# CAN1.net
KiCad netlist of a schematic drawn in Altium Designer
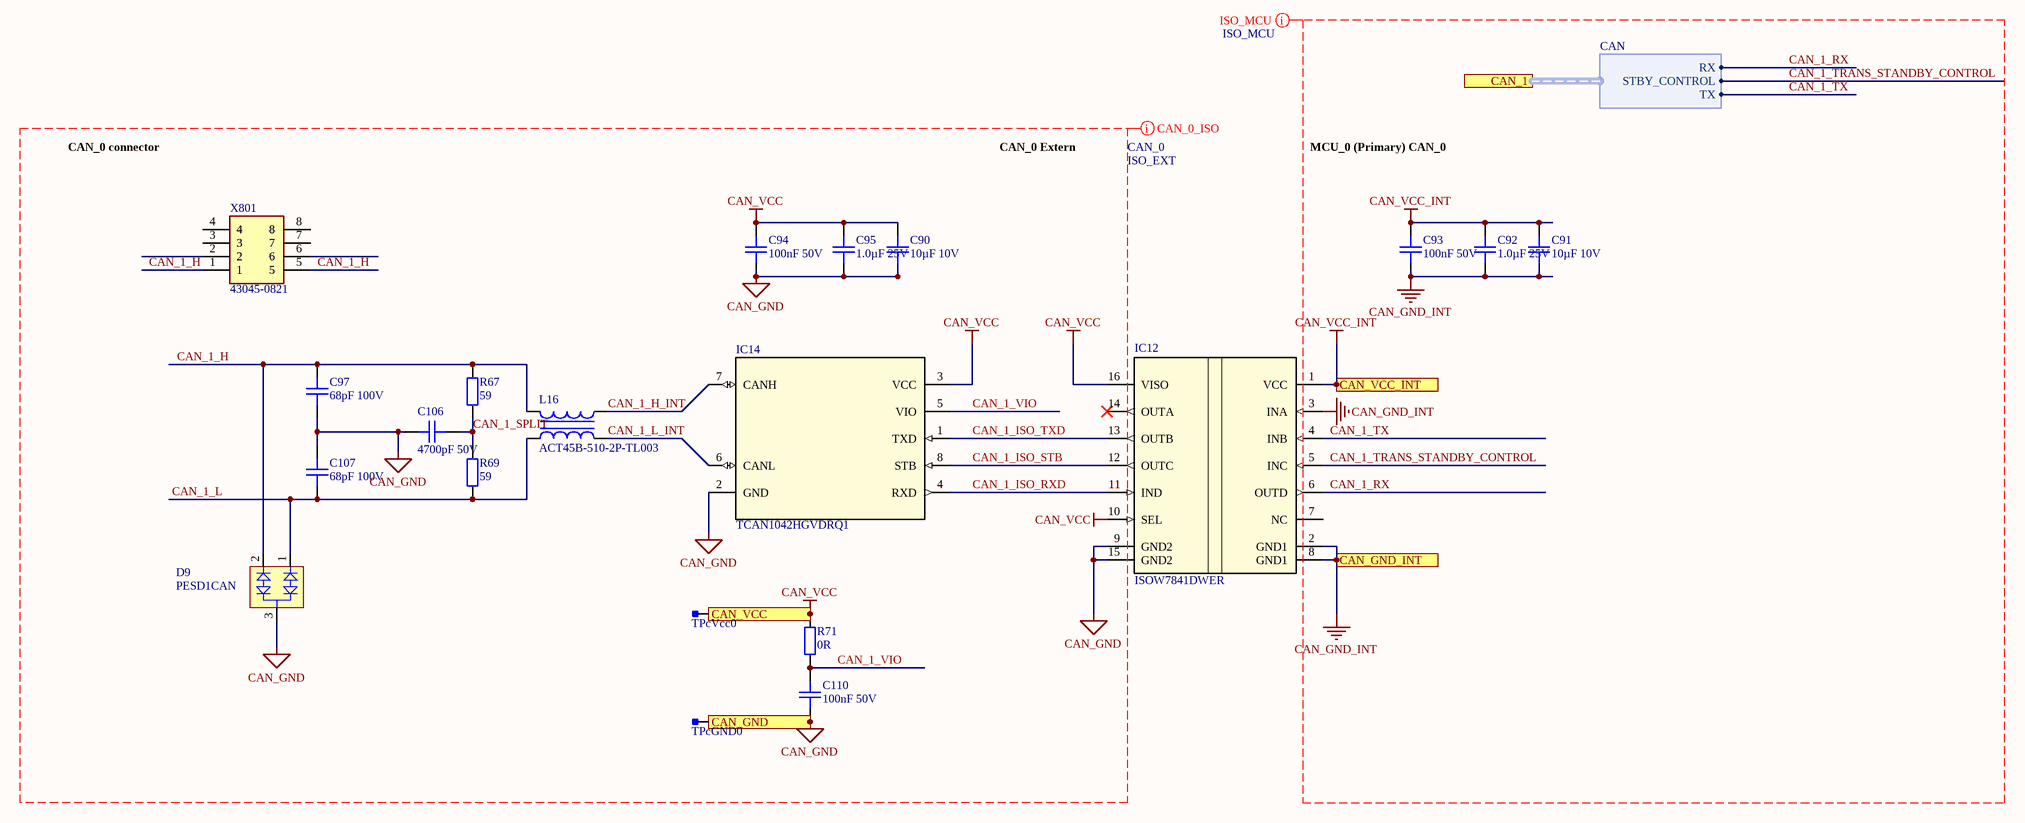
[diagram p0: CAN1.SchDoc]

(export (version "E")
  (design (tool "Eeschema 10.0.6"))
  (components
    (comp (ref "C90")
      (value "10µF 10V")
      (footprint "0805C")
      (description "Ceramic, 10µF, ±10%, 10V, X7R, –55 to 125°C, 0805 (2012),RoHS, Automotive")
      (fields (field (name "PART NUMBER") "GCJ21BR71A106KE01") (field (name "TOLERANCE") "±10%"))
      (libsource (lib "master-010106") (part "gen_C_ceramic_10u_10V_X7R_0805"))
    )
    (comp (ref "C91")
      (value "10µF 10V")
      (footprint "0805C")
      (description "Ceramic, 10µF, ±10%, 10V, X7R, –55 to 125°C, 0805 (2012),RoHS, Automotive")
      (fields (field (name "PART NUMBER") "GCJ21BR71A106KE01") (field (name "TOLERANCE") "±10%"))
      (libsource (lib "master-010106") (part "gen_C_ceramic_10u_10V_X7R_0805"))
    )
    (comp (ref "C92")
      (value "1.0µF 25V")
      (footprint "0603C")
      (description "Ceramic, 1.0µF, ±10%, 25V, X7R, –55 to 125°C, 0603 (1608),RoHS, Automotive")
      (fields (field (name "PART NUMBER") "GCJ188R71E105KA01") (field (name "TOLERANCE") "±10%"))
      (libsource (lib "master-010106") (part "gen_C_ceramic_1u_25V_X7R_0603"))
    )
    (comp (ref "C93")
      (value "100nF 50V")
      (footprint "0603C")
      (description "Ceramic, 100nF, ±10%, 50V, X7R, –55 to 125°C, 0603 (1608),RoHS, Automotive")
      (fields (field (name "PART NUMBER") "GCJ188R71H104KA12") (field (name "TOLERANCE") "±10%"))
      (libsource (lib "master-010106") (part "C"))
    )
    (comp (ref "C94")
      (value "100nF 50V")
      (footprint "0603C")
      (description "Ceramic, 100nF, ±10%, 50V, X7R, –55 to 125°C, 0603 (1608),RoHS, Automotive")
      (fields (field (name "PART NUMBER") "GCJ188R71H104KA12") (field (name "TOLERANCE") "±10%"))
      (libsource (lib "master-010106") (part "C"))
    )
    (comp (ref "C95")
      (value "1.0µF 25V")
      (footprint "0603C")
      (description "Ceramic, 1.0µF, ±10%, 25V, X7R, –55 to 125°C, 0603 (1608),RoHS, Automotive")
      (fields (field (name "PART NUMBER") "GCJ188R71E105KA01") (field (name "TOLERANCE") "±10%"))
      (libsource (lib "master-010106") (part "gen_C_ceramic_1u_25V_X7R_0603"))
    )
    (comp (ref "C97")
      (value "68pF 100V")
      (footprint "0603C")
      (description "Ceramic, 68pF, ±5%, 100V, X7R, 25 to 125°C, 0603 (1608),RoHS, Automotive")
      (fields (field (name "PART NUMBER") "GCM1885C2A680JA16") (field (name "TOLERANCE") "±5%"))
      (libsource (lib "master-010106") (part "gen_C_ceramic_68p_100V_X7R_0603"))
    )
    (comp (ref "C106")
      (value "4700pF 50V")
      (footprint "0603C")
      (description "Ceramic, 4700pF, 0603, ±5%, 50V, C0G")
      (fields (field (name "PART NUMBER") "GRT1885C1H472JA02"))
      (libsource (lib "master-010106") (part "C"))
    )
    (comp (ref "C107")
      (value "68pF 100V")
      (footprint "0603C")
      (description "Ceramic, 68pF, ±5%, 100V, X7R, 25 to 125°C, 0603 (1608),RoHS, Automotive")
      (fields (field (name "PART NUMBER") "GCM1885C2A680JA16") (field (name "TOLERANCE") "±5%"))
      (libsource (lib "master-010106") (part "gen_C_ceramic_68p_100V_X7R_0603"))
    )
    (comp (ref "C110")
      (value "100nF 50V")
      (footprint "0603C")
      (description "Ceramic, 100nF, ±10%, 50V, X7R, –55 to 125°C, 0603 (1608),RoHS, Automotive")
      (fields (field (name "PART NUMBER") "GCJ188R71H104KA12") (field (name "TOLERANCE") "±10%"))
      (libsource (lib "master-010106") (part "C"))
    )
    (comp (ref "D9")
      (value "PESD1CAN")
      (footprint "NXP-SOT23-3_V")
      (description "CAN Bus ESD Protection Diode, 200 W, 24 V, -65 to 150 degC, 3-Pin SOT23, RoHS, Tape and Reel")
      (fields (field (name "MANUFACTURER") "NXP Semiconductors"))
      (libsource (lib "Altium Content Vault") (part "NXP-PESD1CAN-SOT23-3"))
    )
    (comp (ref "IC12")
      (value "ISOW7841DWER")
      (footprint "DWE0016A")
      (description "Imported")
      (fields (field (name "MANUFACTURER") "Texas Instruments"))
      (libsource (lib "ti-import") (part "ISOW7841DWER"))
    )
    (comp (ref "IC14")
      (value "TCAN1042HGVDRQ1")
      (footprint "D0008A_N")
      (description "Imported")
      (fields (field (name "PARTNUMBER") "TCAN1042HGVDQ1") (field (name "MANUFACTURER") "Texas Instruments"))
      (libsource (lib "ti-import") (part "TCAN1042HGVDRQ1"))
    )
    (comp (ref "L16")
      (value "ACT45B-510-2P-TL003")
      (footprint "TDK-ACT45B-510-2P-TL003-4_V")
      (fields (field (name "MANUFACTURER") "TDK"))
      (libsource (lib "Altium Content Vault") (part "TDK-ACXXXXX-XXX-2P-T000-4"))
    )
    (comp (ref "R67")
      (value "59")
      (footprint "0805R")
      (description "SMD Resistor 59R 0805")
      (fields (field (name "PART NUMBER") "gen_R_62R_0603") (field (name "TOLERANCE") "1%"))
      (libsource (lib "master-010106") (part "gen_R_59R_0805"))
    )
    (comp (ref "R69")
      (value "59")
      (footprint "0805R")
      (description "SMD Resistor 59R 0805")
      (fields (field (name "PART NUMBER") "gen_R_62R_0603") (field (name "TOLERANCE") "1%"))
      (libsource (lib "master-010106") (part "gen_R_59R_0805"))
    )
    (comp (ref "R71")
      (value "0R")
      (footprint "0603R")
      (description "SMD Resistor 0R 0603")
      (fields (field (name "PART NUMBER") "gen_R_0R_0603") (field (name "POWER") "0.1W"))
      (libsource (lib "master-010106") (part "gen_R_0R_0603"))
    )
    (comp (ref "TPcGND0")
      (value "Testpoint_Square")
      (footprint "Testpoint_S1")
      (description "Testpoint, square")
      (libsource (lib "OE750") (part "Testpoint_Square"))
    )
    (comp (ref "TPcVcc0")
      (value "Testpoint_Square")
      (footprint "Testpoint_S1")
      (description "Testpoint, square")
      (libsource (lib "OE750") (part "Testpoint_Square"))
    )
    (comp (ref "X801")
      (value "43045-0821")
      (footprint "43045-0821")
      (fields (field (name "MOUSER PART NUMBER") "538-43045-0821"))
      (libsource (lib "SamacSys") (part "43045-0821"))
    )
  )
  (nets
    (net (code "2") (name "/CAN_1_H") (class "Default")
      (node (ref "C97") (pin "2") (pinfunction "2_2") (pintype "passive"))
      (node (ref "D9") (pin "2") (pinfunction "K2_2") (pintype "passive"))
      (node (ref "L16") (pin "2") (pinfunction "2_2") (pintype "passive"))
      (node (ref "R67") (pin "2") (pinfunction "2_2") (pintype "passive"))
      (node (ref "X801") (pin "1") (pinfunction "1_1") (pintype "passive"))
      (node (ref "X801") (pin "5") (pinfunction "5_5") (pintype "passive"))
    )
    (net (code "3") (name "/CAN_1_H_INT") (class "Default")
      (node (ref "IC14") (pin "7") (pinfunction "CANH_7") (pintype "bidirectional"))
      (node (ref "L16") (pin "3") (pinfunction "3_3") (pintype "passive"))
    )
    (net (code "4") (name "/CAN_1_ISO_RXD") (class "Default")
      (node (ref "IC12") (pin "11") (pinfunction "IND_11") (pintype "input"))
      (node (ref "IC14") (pin "4") (pinfunction "RXD_4") (pintype "output"))
    )
    (net (code "5") (name "/CAN_1_ISO_STB") (class "Default")
      (node (ref "IC12") (pin "12") (pinfunction "OUTC_12") (pintype "output"))
      (node (ref "IC14") (pin "8") (pinfunction "STB_8") (pintype "input"))
    )
    (net (code "6") (name "/CAN_1_ISO_TXD") (class "Default")
      (node (ref "IC12") (pin "13") (pinfunction "OUTB_13") (pintype "output"))
      (node (ref "IC14") (pin "1") (pinfunction "TXD_1") (pintype "input"))
    )
    (net (code "7") (name "/CAN_1_L") (class "Default")
      (node (ref "C107") (pin "1") (pinfunction "1_1") (pintype "passive"))
      (node (ref "D9") (pin "1") (pinfunction "K1_1") (pintype "passive"))
      (node (ref "L16") (pin "1") (pinfunction "1_1") (pintype "passive"))
      (node (ref "R69") (pin "1") (pinfunction "1_1") (pintype "passive"))
    )
    (net (code "8") (name "/CAN_1_L_INT") (class "Default")
      (node (ref "IC14") (pin "6") (pinfunction "CANL_6") (pintype "bidirectional"))
      (node (ref "L16") (pin "4") (pinfunction "4_4") (pintype "passive"))
    )
    (net (code "9") (name "/CAN_1_RX") (class "Default")
      (node (ref "IC12") (pin "6") (pinfunction "OUTD_6") (pintype "output"))
    )
    (net (code "10") (name "/CAN_1_SPLIT") (class "Default")
      (node (ref "C106") (pin "2") (pinfunction "2_2") (pintype "passive"))
      (node (ref "R67") (pin "1") (pinfunction "1_1") (pintype "passive"))
      (node (ref "R69") (pin "2") (pinfunction "2_2") (pintype "passive"))
    )
    (net (code "11") (name "/CAN_1_TRANS_STANDBY_CONTROL") (class "Default")
      (node (ref "IC12") (pin "5") (pinfunction "INC_5") (pintype "input"))
    )
    (net (code "12") (name "/CAN_1_TX") (class "Default")
      (node (ref "IC12") (pin "4") (pinfunction "INB_4") (pintype "input"))
    )
    (net (code "13") (name "/CAN_1_VIO") (class "Default")
      (node (ref "C110") (pin "2") (pinfunction "2_2") (pintype "passive"))
      (node (ref "IC14") (pin "5") (pinfunction "VIO_5") (pintype "power_in"))
      (node (ref "R71") (pin "2") (pinfunction "2_2") (pintype "passive"))
    )
    (net (code "15") (name "CAN_GND") (class "Default")
      (node (ref "C106") (pin "1") (pinfunction "1_1") (pintype "passive"))
      (node (ref "C107") (pin "2") (pinfunction "2_2") (pintype "passive"))
      (node (ref "C110") (pin "1") (pinfunction "1_1") (pintype "passive"))
      (node (ref "C90") (pin "2") (pinfunction "2_2") (pintype "passive"))
      (node (ref "C94") (pin "1") (pinfunction "1_1") (pintype "passive"))
      (node (ref "C95") (pin "1") (pinfunction "1_1") (pintype "passive"))
      (node (ref "C97") (pin "1") (pinfunction "1_1") (pintype "passive"))
      (node (ref "D9") (pin "3") (pinfunction "C_3") (pintype "passive"))
      (node (ref "IC12") (pin "15") (pinfunction "GND2_15") (pintype "power_in"))
      (node (ref "IC12") (pin "9") (pinfunction "GND2_9") (pintype "power_in"))
      (node (ref "IC14") (pin "2") (pinfunction "GND_2") (pintype "power_in"))
      (node (ref "TPcGND0") (pin "1") (pinfunction "1_1") (pintype "passive"))
    )
    (net (code "16") (name "CAN_GND_INT") (class "Default")
      (node (ref "C91") (pin "2") (pinfunction "2_2") (pintype "passive"))
      (node (ref "C92") (pin "1") (pinfunction "1_1") (pintype "passive"))
      (node (ref "C93") (pin "1") (pinfunction "1_1") (pintype "passive"))
      (node (ref "IC12") (pin "2") (pinfunction "GND1_2") (pintype "power_in"))
      (node (ref "IC12") (pin "3") (pinfunction "INA_3") (pintype "input"))
      (node (ref "IC12") (pin "8") (pinfunction "GND1_8") (pintype "power_in"))
    )
    (net (code "17") (name "CAN_VCC") (class "Default")
      (node (ref "C90") (pin "1") (pinfunction "1_1") (pintype "passive"))
      (node (ref "C94") (pin "2") (pinfunction "2_2") (pintype "passive"))
      (node (ref "C95") (pin "2") (pinfunction "2_2") (pintype "passive"))
      (node (ref "IC12") (pin "10") (pinfunction "SEL_10") (pintype "input"))
      (node (ref "IC12") (pin "16") (pinfunction "VISO_16") (pintype "power_in"))
      (node (ref "IC14") (pin "3") (pinfunction "VCC_3") (pintype "power_in"))
      (node (ref "R71") (pin "1") (pinfunction "1_1") (pintype "passive"))
      (node (ref "TPcVcc0") (pin "1") (pinfunction "1_1") (pintype "passive"))
    )
    (net (code "18") (name "CAN_VCC_INT") (class "Default")
      (node (ref "C91") (pin "1") (pinfunction "1_1") (pintype "passive"))
      (node (ref "C92") (pin "2") (pinfunction "2_2") (pintype "passive"))
      (node (ref "C93") (pin "2") (pinfunction "2_2") (pintype "passive"))
      (node (ref "IC12") (pin "1") (pinfunction "VCC_1") (pintype "power_in"))
    )
    (net (code "19") (name "unconnected-(IC12-NC-Pad7)") (class "Default")
      (node (ref "IC12") (pin "7") (pinfunction "NC_7") (pintype "passive"))
    )
    (net (code "20") (name "unconnected-(IC12-OUTA-Pad14)") (class "Default")
      (node (ref "IC12") (pin "14") (pinfunction "OUTA_14") (pintype "output+no_connect"))
    )
    (net (code "21") (name "unconnected-(X801-Pad2)") (class "Default")
      (node (ref "X801") (pin "2") (pinfunction "2_2") (pintype "passive"))
    )
    (net (code "22") (name "unconnected-(X801-Pad3)") (class "Default")
      (node (ref "X801") (pin "3") (pinfunction "3_3") (pintype "passive"))
    )
    (net (code "23") (name "unconnected-(X801-Pad4)") (class "Default")
      (node (ref "X801") (pin "4") (pinfunction "4_4") (pintype "passive"))
    )
    (net (code "24") (name "unconnected-(X801-Pad6)") (class "Default")
      (node (ref "X801") (pin "6") (pinfunction "6_6") (pintype "passive"))
    )
    (net (code "25") (name "unconnected-(X801-Pad7)") (class "Default")
      (node (ref "X801") (pin "7") (pinfunction "7_7") (pintype "passive"))
    )
    (net (code "26") (name "unconnected-(X801-Pad8)") (class "Default")
      (node (ref "X801") (pin "8") (pinfunction "8_8") (pintype "passive"))
    )
  )
)
